# GPS.net
KiCad netlist of a schematic drawn in Altium Designer
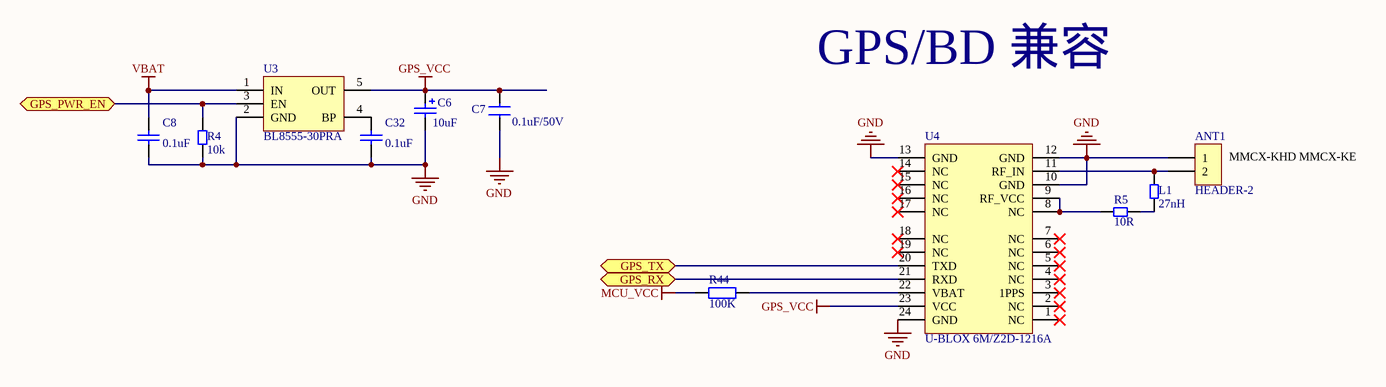
[diagram p0: GPS.SchDoc]

(export (version "E")
  (design (tool "Eeschema 10.0.6"))
  (components
    (comp (ref "ANT1") (value "HEADER-2") (footprint "IPEX") (libsource (lib "Calf") (part "HEADER-2")))
    (comp (ref "C6")
      (value "10uF")
      (footprint "CAP1210")
      (description "Polarized Capacitor (Radial)")
      (fields (field (name "PUBLISHER") "Altium Limited"))
      (libsource (lib "Calf") (part "Cap Pol"))
    )
    (comp (ref "C7") (value "0.1uF/50V") (footprint "0603C") (libsource (lib "0603C") (part "CAP")))
    (comp (ref "C8")
      (value "0.1uF")
      (footprint "0603C")
      (description "Capacitor")
      (fields (field (name "PUBLISHER") "Altium Limited"))
      (libsource (lib "Calf") (part "Cap"))
    )
    (comp (ref "C32")
      (value "0.1uF")
      (footprint "0603C")
      (description "Capacitor")
      (fields (field (name "PUBLISHER") "Altium Limited"))
      (libsource (lib "Calf") (part "Cap"))
    )
    (comp (ref "L1")
      (value "27nH")
      (footprint "0603R")
      (description "Resistor")
      (fields (field (name "PUBLISHER") "Altium Limited"))
      (libsource (lib "Calf") (part "Res2"))
    )
    (comp (ref "R4")
      (value "10k")
      (footprint "0603R")
      (description "Resistor")
      (fields (field (name "PUBLISHER") "Altium Limited"))
      (libsource (lib "Calf") (part "Res2"))
    )
    (comp (ref "R5")
      (value "10R")
      (footprint "1206R")
      (description "Resistor")
      (fields (field (name "PUBLISHER") "Altium Limited"))
      (libsource (lib "") (part "Res2_1"))
    )
    (comp (ref "R44") (value "100K") (footprint "0603R") (libsource (lib "WT4815_CPU_Board") (part "0603R")))
    (comp (ref "U3") (value "BL8555-30PRA") (footprint "SOT23-5") (libsource (lib "Calf") (part "SGM2019")))
    (comp (ref "U4")
      (value "U-BLOX 6M/Z2D-1216A")
      (footprint "G_UBLOXNEO5")
      (libsource (lib "Calf") (part "XBDM-1612"))
    )
  )
  (nets
    (net (code "1") (name "/GPS_PWR_EN") (class "Default")
      (node (ref "R4") (pin "2") (pinfunction "2_2") (pintype "passive"))
      (node (ref "U3") (pin "3") (pinfunction "EN_3") (pintype "passive"))
    )
    (net (code "2") (name "/GPS_RX") (class "Default")
      (node (ref "U4") (pin "21") (pinfunction "RXD_21") (pintype "passive"))
    )
    (net (code "3") (name "/GPS_TX") (class "Default")
      (node (ref "U4") (pin "20") (pinfunction "TXD_20") (pintype "passive"))
    )
    (net (code "4") (name "GND") (class "Default")
      (node (ref "ANT1") (pin "1") (pinfunction "1_1") (pintype "passive"))
      (node (ref "C32") (pin "1") (pinfunction "1_1") (pintype "passive"))
      (node (ref "C6") (pin "2") (pinfunction "2_2") (pintype "passive"))
      (node (ref "C7") (pin "2") (pinfunction "2_2") (pintype "passive"))
      (node (ref "C8") (pin "1") (pinfunction "1_1") (pintype "passive"))
      (node (ref "R4") (pin "1") (pinfunction "1_1") (pintype "passive"))
      (node (ref "U3") (pin "2") (pinfunction "GND_2") (pintype "passive"))
      (node (ref "U4") (pin "10") (pinfunction "GND_10") (pintype "passive"))
      (node (ref "U4") (pin "12") (pinfunction "GND_12") (pintype "passive"))
      (node (ref "U4") (pin "13") (pinfunction "GND_13") (pintype "passive"))
      (node (ref "U4") (pin "24") (pinfunction "GND_24") (pintype "passive"))
    )
    (net (code "5") (name "GPS_VCC") (class "Default")
      (node (ref "C6") (pin "1") (pinfunction "1_1") (pintype "passive"))
      (node (ref "C7") (pin "1") (pinfunction "1_1") (pintype "passive"))
      (node (ref "U3") (pin "5") (pinfunction "OUT_5") (pintype "passive"))
      (node (ref "U4") (pin "23") (pinfunction "VCC_23") (pintype "passive"))
    )
    (net (code "6") (name "MCU_VCC") (class "Default")
      (node (ref "R44") (pin "1") (pinfunction "1_1") (pintype "passive"))
    )
    (net (code "7") (name "Net-(L1-Pad1)") (class "Default")
      (node (ref "L1") (pin "1") (pinfunction "1_1") (pintype "passive"))
      (node (ref "R5") (pin "2") (pinfunction "2_2") (pintype "passive"))
    )
    (net (code "8") (name "Net-(U3-BP)") (class "Default")
      (node (ref "C32") (pin "2") (pinfunction "2_2") (pintype "passive"))
      (node (ref "U3") (pin "4") (pinfunction "BP_4") (pintype "passive"))
    )
    (net (code "9") (name "Net-(U4-RF_IN)") (class "Default")
      (node (ref "ANT1") (pin "2") (pinfunction "2_2") (pintype "passive"))
      (node (ref "L1") (pin "2") (pinfunction "2_2") (pintype "passive"))
      (node (ref "U4") (pin "11") (pinfunction "RF_IN_11") (pintype "passive"))
    )
    (net (code "10") (name "Net-(U4-RF_VCC)") (class "Default")
      (node (ref "R5") (pin "1") (pinfunction "1_1") (pintype "passive"))
      (node (ref "U4") (pin "8") (pinfunction "NC_8") (pintype "passive"))
      (node (ref "U4") (pin "9") (pinfunction "RF_VCC_9") (pintype "passive"))
    )
    (net (code "11") (name "Net-(U4-VBAT)") (class "Default")
      (node (ref "R44") (pin "2") (pinfunction "2_2") (pintype "passive"))
      (node (ref "U4") (pin "22") (pinfunction "VBAT_22") (pintype "passive"))
    )
    (net (code "12") (name "VBAT") (class "Default")
      (node (ref "C8") (pin "2") (pinfunction "2_2") (pintype "passive"))
      (node (ref "U3") (pin "1") (pinfunction "IN_1") (pintype "passive"))
    )
    (net (code "13") (name "unconnected-(U4-1PPS-Pad3)") (class "Default")
      (node (ref "U4") (pin "3") (pinfunction "1PPS_3") (pintype "passive+no_connect"))
    )
    (net (code "14") (name "unconnected-(U4-NC-Pad1)") (class "Default")
      (node (ref "U4") (pin "1") (pinfunction "NC_1") (pintype "passive+no_connect"))
    )
    (net (code "15") (name "unconnected-(U4-NC-Pad2)") (class "Default")
      (node (ref "U4") (pin "2") (pinfunction "NC_2") (pintype "passive+no_connect"))
    )
    (net (code "16") (name "unconnected-(U4-NC-Pad4)") (class "Default")
      (node (ref "U4") (pin "4") (pinfunction "NC_4") (pintype "passive+no_connect"))
    )
    (net (code "17") (name "unconnected-(U4-NC-Pad5)") (class "Default")
      (node (ref "U4") (pin "5") (pinfunction "NC_5") (pintype "passive+no_connect"))
    )
    (net (code "18") (name "unconnected-(U4-NC-Pad6)") (class "Default")
      (node (ref "U4") (pin "6") (pinfunction "NC_6") (pintype "passive+no_connect"))
    )
    (net (code "19") (name "unconnected-(U4-NC-Pad7)") (class "Default")
      (node (ref "U4") (pin "7") (pinfunction "NC_7") (pintype "passive+no_connect"))
    )
    (net (code "20") (name "unconnected-(U4-NC-Pad14)") (class "Default")
      (node (ref "U4") (pin "14") (pinfunction "NC_14") (pintype "passive+no_connect"))
    )
    (net (code "21") (name "unconnected-(U4-NC-Pad15)") (class "Default")
      (node (ref "U4") (pin "15") (pinfunction "NC_15") (pintype "passive+no_connect"))
    )
    (net (code "22") (name "unconnected-(U4-NC-Pad16)") (class "Default")
      (node (ref "U4") (pin "16") (pinfunction "NC_16") (pintype "passive+no_connect"))
    )
    (net (code "23") (name "unconnected-(U4-NC-Pad17)") (class "Default")
      (node (ref "U4") (pin "17") (pinfunction "NC_17") (pintype "passive+no_connect"))
    )
    (net (code "24") (name "unconnected-(U4-NC-Pad18)") (class "Default")
      (node (ref "U4") (pin "18") (pinfunction "NC_18") (pintype "passive+no_connect"))
    )
    (net (code "25") (name "unconnected-(U4-NC-Pad19)") (class "Default")
      (node (ref "U4") (pin "19") (pinfunction "NC_19") (pintype "passive+no_connect"))
    )
  )
)
